# SensorInterface.net
KiCad netlist of a schematic drawn in EAGLE
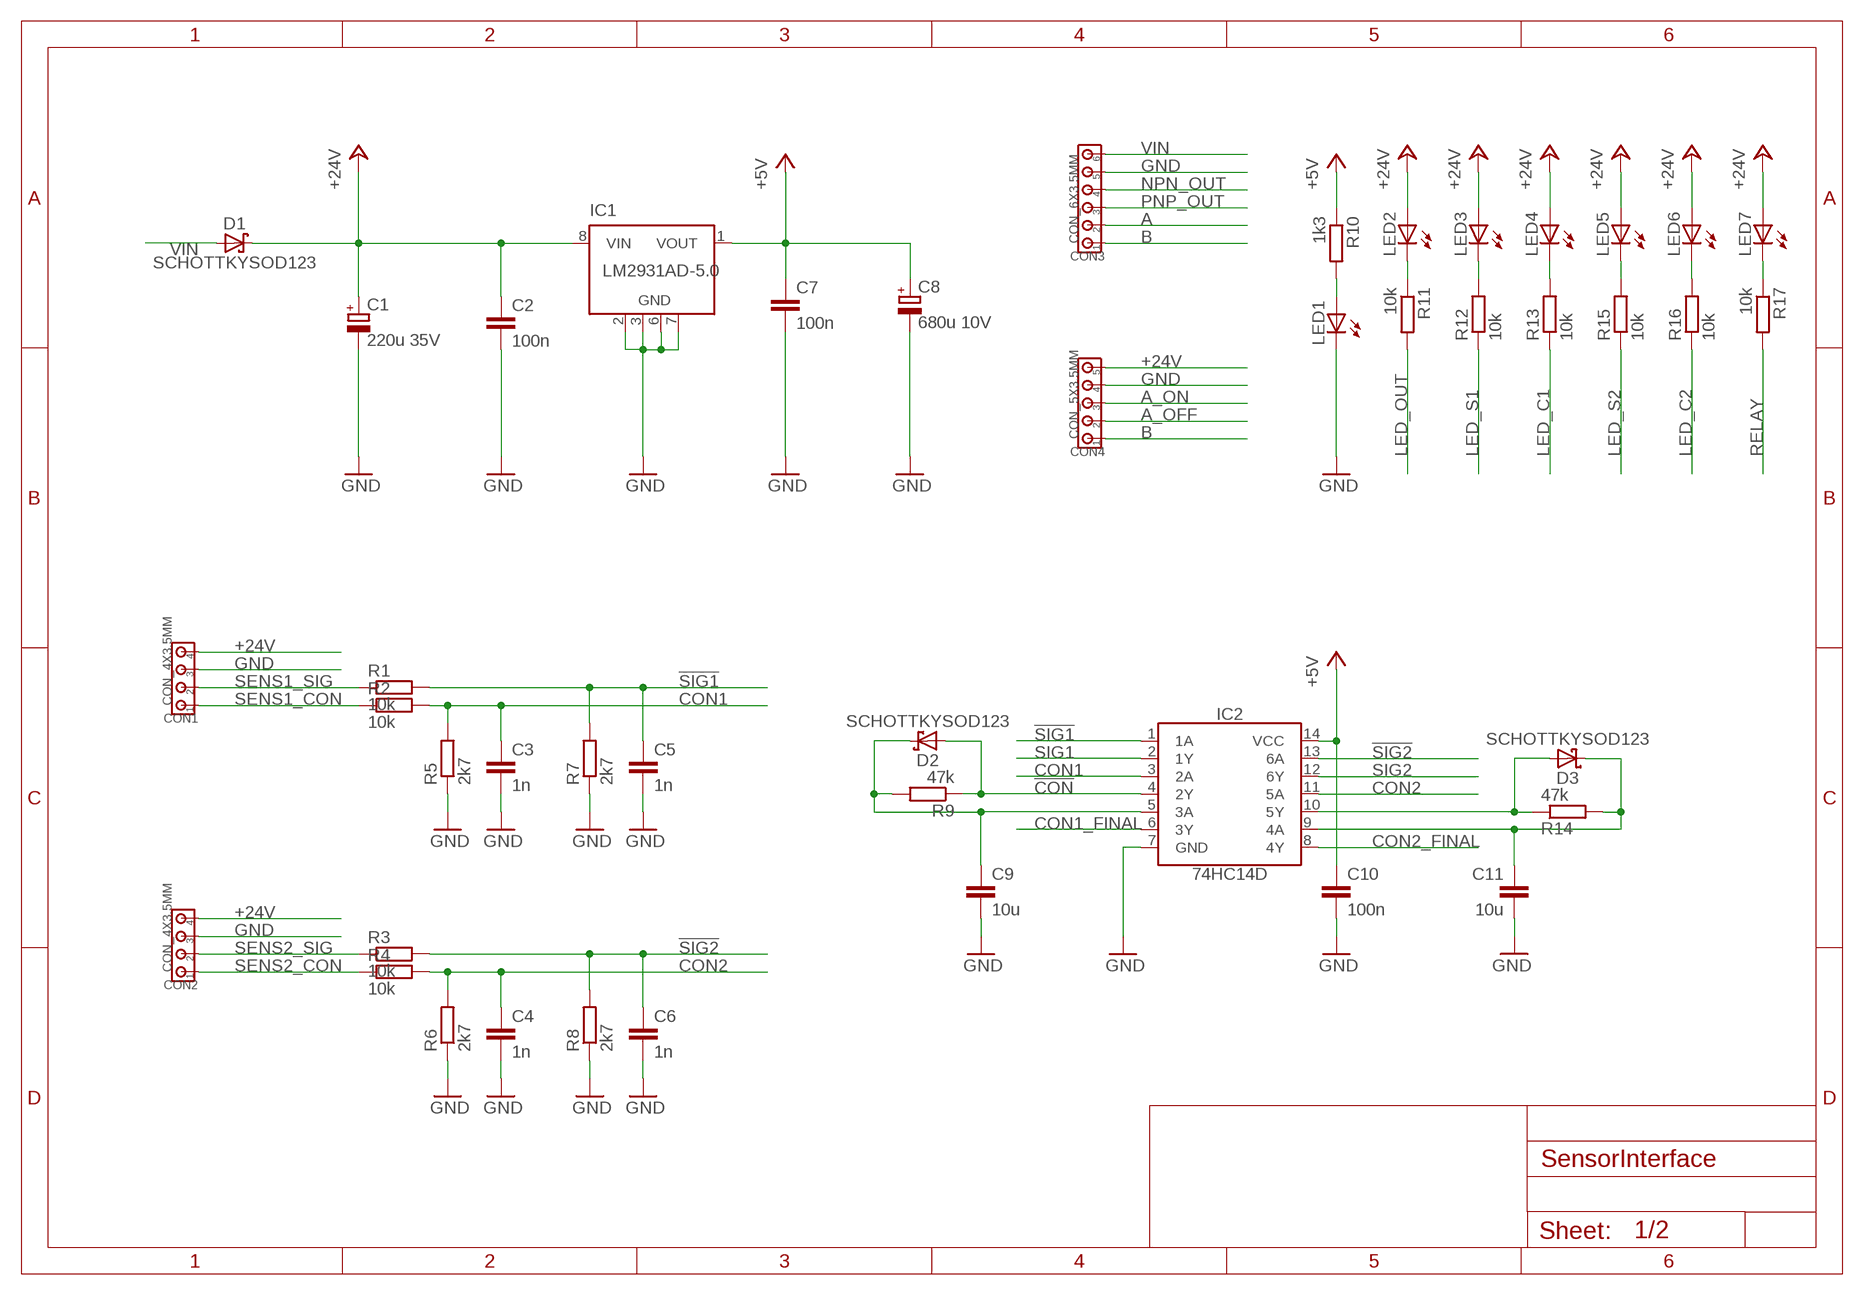
[diagram p0: schematic, sheet 1]
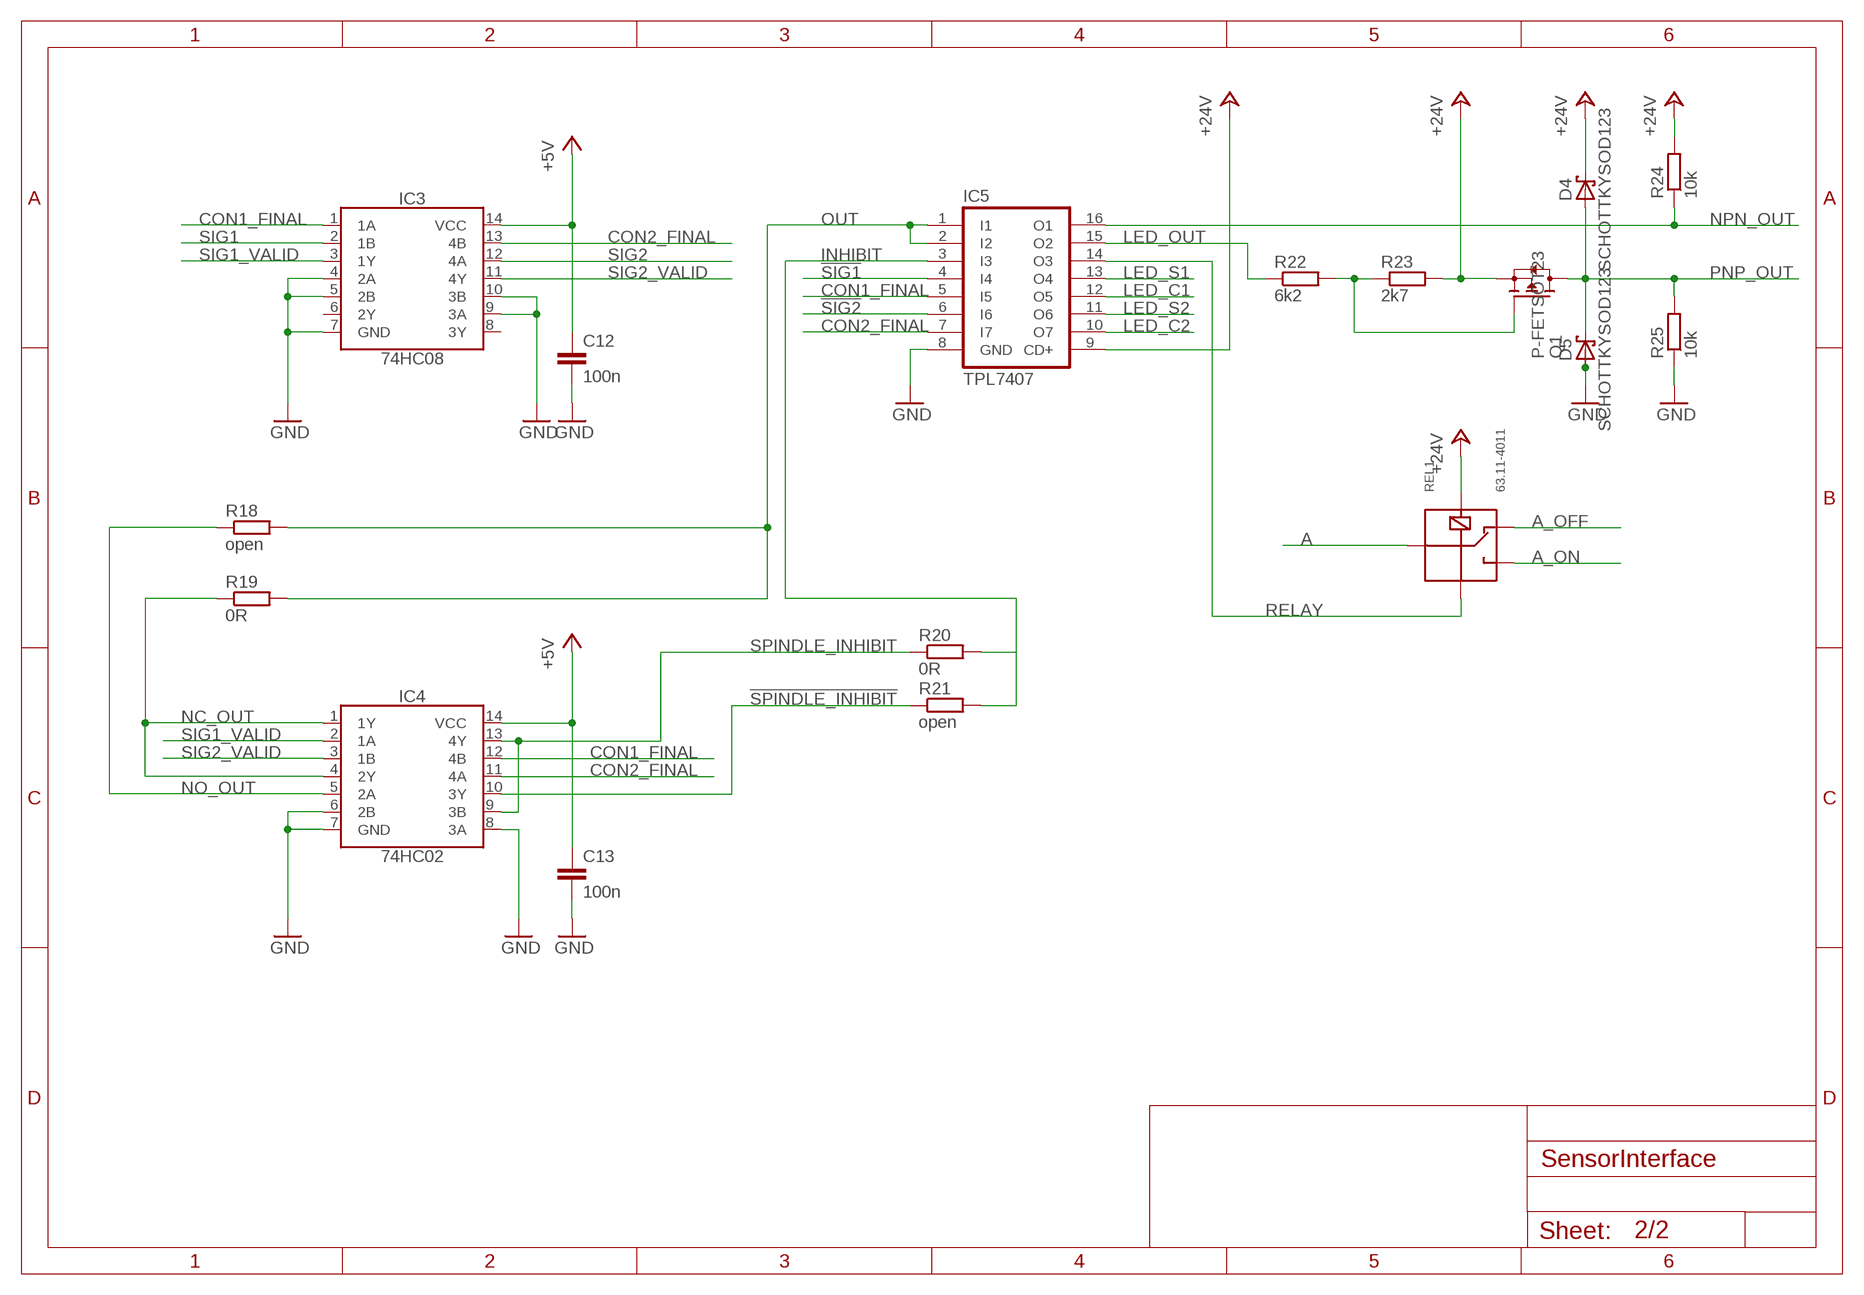
[diagram p1: schematic, sheet 2]

(export (version "E")
  (design (tool "Eeschema 10.0.6"))
  (components
    (comp (ref "C1")
      (value "220u 35V")
      (footprint "eagle-import:8MM")
      (libsource (lib "eagle-import") (part "C_POLARIZED8MM"))
    )
    (comp (ref "C2")
      (value "100n")
      (footprint "eagle-import:C0805")
      (libsource (lib "eagle-import") (part "CC0805"))
    )
    (comp (ref "C3")
      (value "1n")
      (footprint "eagle-import:C0805")
      (libsource (lib "eagle-import") (part "CC0805"))
    )
    (comp (ref "C4")
      (value "1n")
      (footprint "eagle-import:C0805")
      (libsource (lib "eagle-import") (part "CC0805"))
    )
    (comp (ref "C5")
      (value "1n")
      (footprint "eagle-import:C0805")
      (libsource (lib "eagle-import") (part "CC0805"))
    )
    (comp (ref "C6")
      (value "1n")
      (footprint "eagle-import:C0805")
      (libsource (lib "eagle-import") (part "CC0805"))
    )
    (comp (ref "C7")
      (value "100n")
      (footprint "eagle-import:C0805")
      (libsource (lib "eagle-import") (part "CC0805"))
    )
    (comp (ref "C8")
      (value "680u 10V")
      (footprint "eagle-import:8MM")
      (libsource (lib "eagle-import") (part "C_POLARIZED8MM"))
    )
    (comp (ref "C9")
      (value "10u")
      (footprint "eagle-import:C0805")
      (libsource (lib "eagle-import") (part "CC0805"))
    )
    (comp (ref "C10")
      (value "100n")
      (footprint "eagle-import:C0805")
      (libsource (lib "eagle-import") (part "CC0805"))
    )
    (comp (ref "C11")
      (value "10u")
      (footprint "eagle-import:C0805")
      (libsource (lib "eagle-import") (part "CC0805"))
    )
    (comp (ref "CON1")
      (value "CON_4X3.5MM")
      (footprint "eagle-import:3.5MM_4X")
      (libsource (lib "eagle-import") (part "CON_4X3.5MM"))
    )
    (comp (ref "CON2")
      (value "CON_4X3.5MM")
      (footprint "eagle-import:3.5MM_4X")
      (libsource (lib "eagle-import") (part "CON_4X3.5MM"))
    )
    (comp (ref "CON3")
      (value "CON_6X3.5MM")
      (footprint "eagle-import:3.5MM_6X")
      (libsource (lib "eagle-import") (part "CON_6X3.5MM"))
    )
    (comp (ref "CON4")
      (value "CON_5X3.5MM")
      (footprint "eagle-import:3.5MM_5X")
      (libsource (lib "eagle-import") (part "CON_5X3.5MM"))
    )
    (comp (ref "D1")
      (value "SCHOTTKYSOD123")
      (footprint "eagle-import:SOD123")
      (libsource (lib "eagle-import") (part "SCHOTTKYSOD123"))
    )
    (comp (ref "D2")
      (value "SCHOTTKYSOD123")
      (footprint "eagle-import:SOD123")
      (libsource (lib "eagle-import") (part "SCHOTTKYSOD123"))
    )
    (comp (ref "D3")
      (value "SCHOTTKYSOD123")
      (footprint "eagle-import:SOD123")
      (libsource (lib "eagle-import") (part "SCHOTTKYSOD123"))
    )
    (comp (ref "IC1")
      (value "LM2931AD-5.0")
      (footprint "eagle-import:SOIC8")
      (libsource (lib "eagle-import") (part "LM2931AD-5.0"))
    )
    (comp (ref "IC2")
      (value "74HC14D")
      (footprint "eagle-import:SO14")
      (libsource (lib "eagle-import") (part "74HC14D"))
    )
    (comp (ref "LED1")
      (value "LED0805_NB")
      (footprint "eagle-import:LED0805_NOBOARDER")
      (libsource (lib "eagle-import") (part "LED0805_NB"))
    )
    (comp (ref "LED2")
      (value "LED0805_NB")
      (footprint "eagle-import:LED0805_NOBOARDER")
      (libsource (lib "eagle-import") (part "LED0805_NB"))
    )
    (comp (ref "LED3")
      (value "LED0805_NB")
      (footprint "eagle-import:LED0805_NOBOARDER")
      (libsource (lib "eagle-import") (part "LED0805_NB"))
    )
    (comp (ref "LED4")
      (value "LED0805_NB")
      (footprint "eagle-import:LED0805_NOBOARDER")
      (libsource (lib "eagle-import") (part "LED0805_NB"))
    )
    (comp (ref "LED5")
      (value "LED0805_NB")
      (footprint "eagle-import:LED0805_NOBOARDER")
      (libsource (lib "eagle-import") (part "LED0805_NB"))
    )
    (comp (ref "LED6")
      (value "LED0805_NB")
      (footprint "eagle-import:LED0805_NOBOARDER")
      (libsource (lib "eagle-import") (part "LED0805_NB"))
    )
    (comp (ref "LED7")
      (value "LED0805_NB")
      (footprint "eagle-import:LED0805_NOBOARDER")
      (libsource (lib "eagle-import") (part "LED0805_NB"))
    )
    (comp (ref "R1")
      (value "10k")
      (footprint "eagle-import:R0805")
      (libsource (lib "eagle-import") (part "RESISTORR0805"))
    )
    (comp (ref "R2")
      (value "10k")
      (footprint "eagle-import:R0805")
      (libsource (lib "eagle-import") (part "RESISTORR0805"))
    )
    (comp (ref "R3")
      (value "10k")
      (footprint "eagle-import:R0805")
      (libsource (lib "eagle-import") (part "RESISTORR0805"))
    )
    (comp (ref "R4")
      (value "10k")
      (footprint "eagle-import:R0805")
      (libsource (lib "eagle-import") (part "RESISTORR0805"))
    )
    (comp (ref "R5")
      (value "2k7")
      (footprint "eagle-import:R0805")
      (libsource (lib "eagle-import") (part "RESISTORR0805"))
    )
    (comp (ref "R6")
      (value "2k7")
      (footprint "eagle-import:R0805")
      (libsource (lib "eagle-import") (part "RESISTORR0805"))
    )
    (comp (ref "R7")
      (value "2k7")
      (footprint "eagle-import:R0805")
      (libsource (lib "eagle-import") (part "RESISTORR0805"))
    )
    (comp (ref "R8")
      (value "2k7")
      (footprint "eagle-import:R0805")
      (libsource (lib "eagle-import") (part "RESISTORR0805"))
    )
    (comp (ref "R9")
      (value "47k")
      (footprint "eagle-import:R0805")
      (libsource (lib "eagle-import") (part "RESISTORR0805"))
    )
    (comp (ref "R10")
      (value "1k3")
      (footprint "eagle-import:R0805")
      (libsource (lib "eagle-import") (part "RESISTORR0805"))
    )
    (comp (ref "R11")
      (value "10k")
      (footprint "eagle-import:R0805")
      (libsource (lib "eagle-import") (part "RESISTORR0805"))
    )
    (comp (ref "R12")
      (value "10k")
      (footprint "eagle-import:R0805")
      (libsource (lib "eagle-import") (part "RESISTORR0805"))
    )
    (comp (ref "R13")
      (value "10k")
      (footprint "eagle-import:R0805")
      (libsource (lib "eagle-import") (part "RESISTORR0805"))
    )
    (comp (ref "R14")
      (value "47k")
      (footprint "eagle-import:R0805")
      (libsource (lib "eagle-import") (part "RESISTORR0805"))
    )
    (comp (ref "R15")
      (value "10k")
      (footprint "eagle-import:R0805")
      (libsource (lib "eagle-import") (part "RESISTORR0805"))
    )
    (comp (ref "R16")
      (value "10k")
      (footprint "eagle-import:R0805")
      (libsource (lib "eagle-import") (part "RESISTORR0805"))
    )
    (comp (ref "R17")
      (value "10k")
      (footprint "eagle-import:R0805")
      (libsource (lib "eagle-import") (part "RESISTORR0805"))
    )
    (comp (ref "C12")
      (value "100n")
      (footprint "eagle-import:C0805")
      (libsource (lib "eagle-import") (part "CC0805"))
    )
    (comp (ref "C13")
      (value "100n")
      (footprint "eagle-import:C0805")
      (libsource (lib "eagle-import") (part "CC0805"))
    )
    (comp (ref "D4")
      (value "SCHOTTKYSOD123")
      (footprint "eagle-import:SOD123")
      (libsource (lib "eagle-import") (part "SCHOTTKYSOD123"))
    )
    (comp (ref "D5")
      (value "SCHOTTKYSOD123")
      (footprint "eagle-import:SOD123")
      (libsource (lib "eagle-import") (part "SCHOTTKYSOD123"))
    )
    (comp (ref "IC3")
      (value "74HC08")
      (footprint "eagle-import:SO14")
      (libsource (lib "eagle-import") (part "74HC08"))
    )
    (comp (ref "IC4")
      (value "74HC02")
      (footprint "eagle-import:SO14")
      (libsource (lib "eagle-import") (part "74HC02"))
    )
    (comp (ref "IC5")
      (value "TPL7407")
      (footprint "eagle-import:SO16")
      (libsource (lib "eagle-import") (part "ULN2003"))
    )
    (comp (ref "Q1")
      (value "P-FETSOT23")
      (footprint "eagle-import:SOT23")
      (libsource (lib "eagle-import") (part "P-FETSOT23"))
    )
    (comp (ref "R18")
      (value "open")
      (footprint "eagle-import:R0805")
      (libsource (lib "eagle-import") (part "RESISTORR0805"))
    )
    (comp (ref "R19")
      (value "0R")
      (footprint "eagle-import:R0805")
      (libsource (lib "eagle-import") (part "RESISTORR0805"))
    )
    (comp (ref "R20")
      (value "0R")
      (footprint "eagle-import:R0805")
      (libsource (lib "eagle-import") (part "RESISTORR0805"))
    )
    (comp (ref "R21")
      (value "open")
      (footprint "eagle-import:R0805")
      (libsource (lib "eagle-import") (part "RESISTORR0805"))
    )
    (comp (ref "R22")
      (value "6k2")
      (footprint "eagle-import:R0805")
      (libsource (lib "eagle-import") (part "RESISTORR0805"))
    )
    (comp (ref "R23")
      (value "2k7")
      (footprint "eagle-import:R0805")
      (libsource (lib "eagle-import") (part "RESISTORR0805"))
    )
    (comp (ref "R24")
      (value "10k")
      (footprint "eagle-import:R0805")
      (libsource (lib "eagle-import") (part "RESISTORR0805"))
    )
    (comp (ref "R25")
      (value "10k")
      (footprint "eagle-import:R0805")
      (libsource (lib "eagle-import") (part "RESISTORR0805"))
    )
    (comp (ref "REL1")
      (value "63.11-4011")
      (footprint "eagle-import:G5LE")
      (libsource (lib "eagle-import") (part "63.11-4011"))
    )
  )
  (nets
    (net (code "1") (name "+5V") (class "Default")
      (node (ref "C10") (pin "1") (pinfunction "1_1") (pintype "passive"))
      (node (ref "C12") (pin "1") (pinfunction "1_1") (pintype "passive"))
      (node (ref "C13") (pin "1") (pinfunction "1_1") (pintype "passive"))
      (node (ref "C7") (pin "1") (pinfunction "1_1") (pintype "passive"))
      (node (ref "C8") (pin "+") (pinfunction "+_+") (pintype "passive"))
      (node (ref "IC1") (pin "1") (pinfunction "VOUT_1") (pintype "output"))
      (node (ref "IC2") (pin "14") (pinfunction "VCC_14") (pintype "power_in"))
      (node (ref "IC3") (pin "14") (pinfunction "VCC_14") (pintype "power_in"))
      (node (ref "IC4") (pin "14") (pinfunction "VCC_14") (pintype "power_in"))
      (node (ref "R10") (pin "1") (pinfunction "1_1") (pintype "passive"))
    )
    (net (code "2") (name "+24V") (class "Default")
      (node (ref "C1") (pin "+") (pinfunction "+_+") (pintype "passive"))
      (node (ref "C2") (pin "1") (pinfunction "1_1") (pintype "passive"))
      (node (ref "CON1") (pin "4") (pinfunction "4_4") (pintype "passive"))
      (node (ref "CON2") (pin "4") (pinfunction "4_4") (pintype "passive"))
      (node (ref "CON4") (pin "5") (pinfunction "5_5") (pintype "passive"))
      (node (ref "D1") (pin "C") (pinfunction "C_C") (pintype "passive"))
      (node (ref "D4") (pin "C") (pinfunction "C_C") (pintype "passive"))
      (node (ref "IC1") (pin "8") (pinfunction "VIN_8") (pintype "passive"))
      (node (ref "IC5") (pin "9") (pinfunction "CD+_9") (pintype "passive"))
      (node (ref "LED2") (pin "A") (pinfunction "A_A") (pintype "passive"))
      (node (ref "LED3") (pin "A") (pinfunction "A_A") (pintype "passive"))
      (node (ref "LED4") (pin "A") (pinfunction "A_A") (pintype "passive"))
      (node (ref "LED5") (pin "A") (pinfunction "A_A") (pintype "passive"))
      (node (ref "LED6") (pin "A") (pinfunction "A_A") (pintype "passive"))
      (node (ref "LED7") (pin "A") (pinfunction "A_A") (pintype "passive"))
      (node (ref "Q1") (pin "2") (pinfunction "S_2") (pintype "passive"))
      (node (ref "R23") (pin "2") (pinfunction "2_2") (pintype "passive"))
      (node (ref "R24") (pin "2") (pinfunction "2_2") (pintype "passive"))
      (node (ref "REL1") (pin "2") (pinfunction "2_2") (pintype "passive"))
    )
    (net (code "3") (name "A") (class "Default")
      (node (ref "CON3") (pin "2") (pinfunction "2_2") (pintype "passive"))
      (node (ref "REL1") (pin "COM") (pinfunction "COM_COM") (pintype "passive"))
    )
    (net (code "4") (name "A_OFF") (class "Default")
      (node (ref "CON4") (pin "2") (pinfunction "2_2") (pintype "passive"))
      (node (ref "REL1") (pin "O") (pinfunction "O_O") (pintype "passive"))
    )
    (net (code "5") (name "A_ON") (class "Default")
      (node (ref "CON4") (pin "3") (pinfunction "3_3") (pintype "passive"))
      (node (ref "REL1") (pin "C") (pinfunction "C_C") (pintype "passive"))
    )
    (net (code "6") (name "B") (class "Default")
      (node (ref "CON3") (pin "1") (pinfunction "1_1") (pintype "passive"))
      (node (ref "CON4") (pin "1") (pinfunction "1_1") (pintype "passive"))
    )
    (net (code "7") (name "CON1") (class "Default")
      (node (ref "C3") (pin "1") (pinfunction "1_1") (pintype "passive"))
      (node (ref "IC2") (pin "3") (pinfunction "2A_3") (pintype "input"))
      (node (ref "R2") (pin "2") (pinfunction "2_2") (pintype "passive"))
      (node (ref "R5") (pin "2") (pinfunction "2_2") (pintype "passive"))
    )
    (net (code "8") (name "CON1_FINAL") (class "Default")
      (node (ref "IC2") (pin "6") (pinfunction "3Y_6") (pintype "input"))
      (node (ref "IC3") (pin "1") (pinfunction "1A_1") (pintype "input"))
      (node (ref "IC4") (pin "12") (pinfunction "4B_12") (pintype "bidirectional"))
      (node (ref "IC5") (pin "5") (pinfunction "I5_5") (pintype "input"))
    )
    (net (code "9") (name "CON2") (class "Default")
      (node (ref "C4") (pin "1") (pinfunction "1_1") (pintype "passive"))
      (node (ref "IC2") (pin "11") (pinfunction "5A_11") (pintype "bidirectional"))
      (node (ref "R4") (pin "2") (pinfunction "2_2") (pintype "passive"))
      (node (ref "R6") (pin "2") (pinfunction "2_2") (pintype "passive"))
    )
    (net (code "10") (name "CON2_FINAL") (class "Default")
      (node (ref "IC2") (pin "8") (pinfunction "4Y_8") (pintype "bidirectional"))
      (node (ref "IC3") (pin "13") (pinfunction "4B_13") (pintype "bidirectional"))
      (node (ref "IC4") (pin "11") (pinfunction "4A_11") (pintype "bidirectional"))
      (node (ref "IC5") (pin "7") (pinfunction "I7_7") (pintype "input"))
    )
    (net (code "11") (name "GND") (class "Default")
      (node (ref "C1") (pin "-") (pinfunction "-_-") (pintype "passive"))
      (node (ref "C10") (pin "2") (pinfunction "2_2") (pintype "passive"))
      (node (ref "C11") (pin "2") (pinfunction "2_2") (pintype "passive"))
      (node (ref "C12") (pin "2") (pinfunction "2_2") (pintype "passive"))
      (node (ref "C13") (pin "2") (pinfunction "2_2") (pintype "passive"))
      (node (ref "C2") (pin "2") (pinfunction "2_2") (pintype "passive"))
      (node (ref "C3") (pin "2") (pinfunction "2_2") (pintype "passive"))
      (node (ref "C4") (pin "2") (pinfunction "2_2") (pintype "passive"))
      (node (ref "C5") (pin "2") (pinfunction "2_2") (pintype "passive"))
      (node (ref "C6") (pin "2") (pinfunction "2_2") (pintype "passive"))
      (node (ref "C7") (pin "2") (pinfunction "2_2") (pintype "passive"))
      (node (ref "C8") (pin "-") (pinfunction "-_-") (pintype "passive"))
      (node (ref "C9") (pin "2") (pinfunction "2_2") (pintype "passive"))
      (node (ref "CON1") (pin "3") (pinfunction "3_3") (pintype "passive"))
      (node (ref "CON2") (pin "3") (pinfunction "3_3") (pintype "passive"))
      (node (ref "CON3") (pin "5") (pinfunction "5_5") (pintype "passive"))
      (node (ref "CON4") (pin "4") (pinfunction "4_4") (pintype "passive"))
      (node (ref "D5") (pin "A") (pinfunction "A_A") (pintype "passive"))
      (node (ref "IC1") (pin "2") (pinfunction "GND_2") (pintype "power_in"))
      (node (ref "IC1") (pin "3") (pinfunction "GND_3") (pintype "power_in"))
      (node (ref "IC1") (pin "6") (pinfunction "GND_6") (pintype "power_in"))
      (node (ref "IC1") (pin "7") (pinfunction "GND_7") (pintype "power_in"))
      (node (ref "IC2") (pin "7") (pinfunction "GND_7") (pintype "bidirectional"))
      (node (ref "IC3") (pin "10") (pinfunction "3B_10") (pintype "bidirectional"))
      (node (ref "IC3") (pin "4") (pinfunction "2A_4") (pintype "input"))
      (node (ref "IC3") (pin "5") (pinfunction "2B_5") (pintype "input"))
      (node (ref "IC3") (pin "7") (pinfunction "GND_7") (pintype "bidirectional"))
      (node (ref "IC3") (pin "9") (pinfunction "3A_9") (pintype "bidirectional"))
      (node (ref "IC4") (pin "6") (pinfunction "2B_6") (pintype "input"))
      (node (ref "IC4") (pin "7") (pinfunction "GND_7") (pintype "bidirectional"))
      (node (ref "IC4") (pin "8") (pinfunction "3A_8") (pintype "bidirectional"))
      (node (ref "IC5") (pin "8") (pinfunction "GND_8") (pintype "power_in"))
      (node (ref "LED1") (pin "C") (pinfunction "C_C") (pintype "passive"))
      (node (ref "R25") (pin "1") (pinfunction "1_1") (pintype "passive"))
      (node (ref "R5") (pin "1") (pinfunction "1_1") (pintype "passive"))
      (node (ref "R6") (pin "1") (pinfunction "1_1") (pintype "passive"))
      (node (ref "R7") (pin "1") (pinfunction "1_1") (pintype "passive"))
      (node (ref "R8") (pin "1") (pinfunction "1_1") (pintype "passive"))
    )
    (net (code "12") (name "INHIBIT") (class "Default")
      (node (ref "IC5") (pin "3") (pinfunction "I3_3") (pintype "input"))
      (node (ref "R20") (pin "2") (pinfunction "2_2") (pintype "passive"))
      (node (ref "R21") (pin "2") (pinfunction "2_2") (pintype "passive"))
    )
    (net (code "13") (name "LED_C1") (class "Default")
      (node (ref "IC5") (pin "12") (pinfunction "O5_12") (pintype "open_collector"))
      (node (ref "R13") (pin "1") (pinfunction "1_1") (pintype "passive"))
    )
    (net (code "14") (name "LED_C2") (class "Default")
      (node (ref "IC5") (pin "10") (pinfunction "O7_10") (pintype "open_collector"))
      (node (ref "R16") (pin "1") (pinfunction "1_1") (pintype "passive"))
    )
    (net (code "15") (name "LED_OUT") (class "Default")
      (node (ref "IC5") (pin "15") (pinfunction "O2_15") (pintype "open_collector"))
      (node (ref "R11") (pin "2") (pinfunction "2_2") (pintype "passive"))
      (node (ref "R22") (pin "1") (pinfunction "1_1") (pintype "passive"))
    )
    (net (code "16") (name "LED_S1") (class "Default")
      (node (ref "IC5") (pin "13") (pinfunction "O4_13") (pintype "open_collector"))
      (node (ref "R12") (pin "1") (pinfunction "1_1") (pintype "passive"))
    )
    (net (code "17") (name "LED_S2") (class "Default")
      (node (ref "IC5") (pin "11") (pinfunction "O6_11") (pintype "open_collector"))
      (node (ref "R15") (pin "1") (pinfunction "1_1") (pintype "passive"))
    )
    (net (code "18") (name "NC_OUT") (class "Default")
      (node (ref "IC4") (pin "1") (pinfunction "1Y_1") (pintype "input"))
      (node (ref "IC4") (pin "4") (pinfunction "2Y_4") (pintype "input"))
      (node (ref "R19") (pin "1") (pinfunction "1_1") (pintype "passive"))
    )
    (net (code "19") (name "NO_OUT") (class "Default")
      (node (ref "IC4") (pin "5") (pinfunction "2A_5") (pintype "input"))
      (node (ref "R18") (pin "1") (pinfunction "1_1") (pintype "passive"))
    )
    (net (code "20") (name "NPN_OUT") (class "Default")
      (node (ref "CON3") (pin "4") (pinfunction "4_4") (pintype "passive"))
      (node (ref "IC5") (pin "16") (pinfunction "O1_16") (pintype "open_collector"))
      (node (ref "R24") (pin "1") (pinfunction "1_1") (pintype "passive"))
    )
    (net (code "21") (name "Net-(IC2-3A)") (class "Default")
      (node (ref "C9") (pin "1") (pinfunction "1_1") (pintype "passive"))
      (node (ref "D2") (pin "C") (pinfunction "C_C") (pintype "passive"))
      (node (ref "IC2") (pin "5") (pinfunction "3A_5") (pintype "input"))
      (node (ref "R9") (pin "2") (pinfunction "2_2") (pintype "passive"))
    )
    (net (code "22") (name "Net-(IC2-4A)") (class "Default")
      (node (ref "C11") (pin "1") (pinfunction "1_1") (pintype "passive"))
      (node (ref "D3") (pin "C") (pinfunction "C_C") (pintype "passive"))
      (node (ref "IC2") (pin "9") (pinfunction "4A_9") (pintype "bidirectional"))
      (node (ref "R14") (pin "2") (pinfunction "2_2") (pintype "passive"))
    )
    (net (code "23") (name "Net-(IC2-5Y)") (class "Default")
      (node (ref "D3") (pin "A") (pinfunction "A_A") (pintype "passive"))
      (node (ref "IC2") (pin "10") (pinfunction "5Y_10") (pintype "bidirectional"))
      (node (ref "R14") (pin "1") (pinfunction "1_1") (pintype "passive"))
    )
    (net (code "24") (name "Net-(LED1-PadA)") (class "Default")
      (node (ref "LED1") (pin "A") (pinfunction "A_A") (pintype "passive"))
      (node (ref "R10") (pin "2") (pinfunction "2_2") (pintype "passive"))
    )
    (net (code "25") (name "Net-(LED2-PadC)") (class "Default")
      (node (ref "LED2") (pin "C") (pinfunction "C_C") (pintype "passive"))
      (node (ref "R11") (pin "1") (pinfunction "1_1") (pintype "passive"))
    )
    (net (code "26") (name "Net-(LED3-PadC)") (class "Default")
      (node (ref "LED3") (pin "C") (pinfunction "C_C") (pintype "passive"))
      (node (ref "R12") (pin "2") (pinfunction "2_2") (pintype "passive"))
    )
    (net (code "27") (name "Net-(LED4-PadC)") (class "Default")
      (node (ref "LED4") (pin "C") (pinfunction "C_C") (pintype "passive"))
      (node (ref "R13") (pin "2") (pinfunction "2_2") (pintype "passive"))
    )
    (net (code "28") (name "Net-(LED5-PadC)") (class "Default")
      (node (ref "LED5") (pin "C") (pinfunction "C_C") (pintype "passive"))
      (node (ref "R15") (pin "2") (pinfunction "2_2") (pintype "passive"))
    )
    (net (code "29") (name "Net-(LED6-PadC)") (class "Default")
      (node (ref "LED6") (pin "C") (pinfunction "C_C") (pintype "passive"))
      (node (ref "R16") (pin "2") (pinfunction "2_2") (pintype "passive"))
    )
    (net (code "30") (name "Net-(LED7-PadC)") (class "Default")
      (node (ref "LED7") (pin "C") (pinfunction "C_C") (pintype "passive"))
      (node (ref "R17") (pin "1") (pinfunction "1_1") (pintype "passive"))
    )
    (net (code "31") (name "Net-(Q1-G)") (class "Default")
      (node (ref "Q1") (pin "1") (pinfunction "G_1") (pintype "passive"))
      (node (ref "R22") (pin "2") (pinfunction "2_2") (pintype "passive"))
      (node (ref "R23") (pin "1") (pinfunction "1_1") (pintype "passive"))
    )
    (net (code "32") (name "OUT") (class "Default")
      (node (ref "IC5") (pin "1") (pinfunction "I1_1") (pintype "input"))
      (node (ref "IC5") (pin "2") (pinfunction "I2_2") (pintype "input"))
      (node (ref "R18") (pin "2") (pinfunction "2_2") (pintype "passive"))
      (node (ref "R19") (pin "2") (pinfunction "2_2") (pintype "passive"))
    )
    (net (code "33") (name "PNP_OUT") (class "Default")
      (node (ref "CON3") (pin "3") (pinfunction "3_3") (pintype "passive"))
      (node (ref "D4") (pin "A") (pinfunction "A_A") (pintype "passive"))
      (node (ref "D5") (pin "C") (pinfunction "C_C") (pintype "passive"))
      (node (ref "Q1") (pin "3") (pinfunction "D_3") (pintype "passive"))
      (node (ref "R25") (pin "2") (pinfunction "2_2") (pintype "passive"))
    )
    (net (code "34") (name "RELAY") (class "Default")
      (node (ref "IC5") (pin "14") (pinfunction "O3_14") (pintype "open_collector"))
      (node (ref "R17") (pin "2") (pinfunction "2_2") (pintype "passive"))
      (node (ref "REL1") (pin "1") (pinfunction "1_1") (pintype "passive"))
    )
    (net (code "35") (name "SENS1_CON") (class "Default")
      (node (ref "CON1") (pin "1") (pinfunction "1_1") (pintype "passive"))
      (node (ref "R2") (pin "1") (pinfunction "1_1") (pintype "passive"))
    )
    (net (code "36") (name "SENS1_SIG") (class "Default")
      (node (ref "CON1") (pin "2") (pinfunction "2_2") (pintype "passive"))
      (node (ref "R1") (pin "1") (pinfunction "1_1") (pintype "passive"))
    )
    (net (code "37") (name "SENS2_CON") (class "Default")
      (node (ref "CON2") (pin "1") (pinfunction "1_1") (pintype "passive"))
      (node (ref "R4") (pin "1") (pinfunction "1_1") (pintype "passive"))
    )
    (net (code "38") (name "SENS2_SIG") (class "Default")
      (node (ref "CON2") (pin "2") (pinfunction "2_2") (pintype "passive"))
      (node (ref "R3") (pin "1") (pinfunction "1_1") (pintype "passive"))
    )
    (net (code "39") (name "SIG1") (class "Default")
      (node (ref "IC2") (pin "2") (pinfunction "1Y_2") (pintype "input"))
      (node (ref "IC3") (pin "2") (pinfunction "1B_2") (pintype "input"))
    )
    (net (code "40") (name "SIG1_VALID") (class "Default")
      (node (ref "IC3") (pin "3") (pinfunction "1Y_3") (pintype "input"))
      (node (ref "IC4") (pin "2") (pinfunction "1A_2") (pintype "input"))
    )
    (net (code "41") (name "SIG2") (class "Default")
      (node (ref "IC2") (pin "12") (pinfunction "6Y_12") (pintype "bidirectional"))
      (node (ref "IC3") (pin "12") (pinfunction "4A_12") (pintype "bidirectional"))
    )
    (net (code "42") (name "SIG2_VALID") (class "Default")
      (node (ref "IC3") (pin "11") (pinfunction "4Y_11") (pintype "bidirectional"))
      (node (ref "IC4") (pin "3") (pinfunction "1B_3") (pintype "input"))
    )
    (net (code "43") (name "SPINDLE_INHIBIT") (class "Default")
      (node (ref "IC4") (pin "13") (pinfunction "4Y_13") (pintype "bidirectional"))
      (node (ref "IC4") (pin "9") (pinfunction "3B_9") (pintype "bidirectional"))
      (node (ref "R20") (pin "1") (pinfunction "1_1") (pintype "passive"))
    )
    (net (code "44") (name "VIN") (class "Default")
      (node (ref "CON3") (pin "6") (pinfunction "6_6") (pintype "passive"))
      (node (ref "D1") (pin "A") (pinfunction "A_A") (pintype "passive"))
    )
    (net (code "45") (name "unconnected-(IC3-2Y-Pad6)") (class "Default")
      (node (ref "IC3") (pin "6") (pinfunction "2Y_6") (pintype "input"))
    )
    (net (code "46") (name "unconnected-(IC3-3Y-Pad8)") (class "Default")
      (node (ref "IC3") (pin "8") (pinfunction "3Y_8") (pintype "bidirectional"))
    )
    (net (code "47") (name "~{CON}") (class "Default")
      (node (ref "D2") (pin "A") (pinfunction "A_A") (pintype "passive"))
      (node (ref "IC2") (pin "4") (pinfunction "2Y_4") (pintype "input"))
      (node (ref "R9") (pin "1") (pinfunction "1_1") (pintype "passive"))
    )
    (net (code "48") (name "~{SIG1}") (class "Default")
      (node (ref "C5") (pin "1") (pinfunction "1_1") (pintype "passive"))
      (node (ref "IC2") (pin "1") (pinfunction "1A_1") (pintype "input"))
      (node (ref "IC5") (pin "4") (pinfunction "I4_4") (pintype "input"))
      (node (ref "R1") (pin "2") (pinfunction "2_2") (pintype "passive"))
      (node (ref "R7") (pin "2") (pinfunction "2_2") (pintype "passive"))
    )
    (net (code "49") (name "~{SIG2}") (class "Default")
      (node (ref "C6") (pin "1") (pinfunction "1_1") (pintype "passive"))
      (node (ref "IC2") (pin "13") (pinfunction "6A_13") (pintype "bidirectional"))
      (node (ref "IC5") (pin "6") (pinfunction "I6_6") (pintype "input"))
      (node (ref "R3") (pin "2") (pinfunction "2_2") (pintype "passive"))
      (node (ref "R8") (pin "2") (pinfunction "2_2") (pintype "passive"))
    )
    (net (code "50") (name "~{SPINDLE_INHIBIT}") (class "Default")
      (node (ref "IC4") (pin "10") (pinfunction "3Y_10") (pintype "bidirectional"))
      (node (ref "R21") (pin "1") (pinfunction "1_1") (pintype "passive"))
    )
  )
)
